# 04_SCAN.net
KiCad netlist of a schematic drawn in Altium Designer
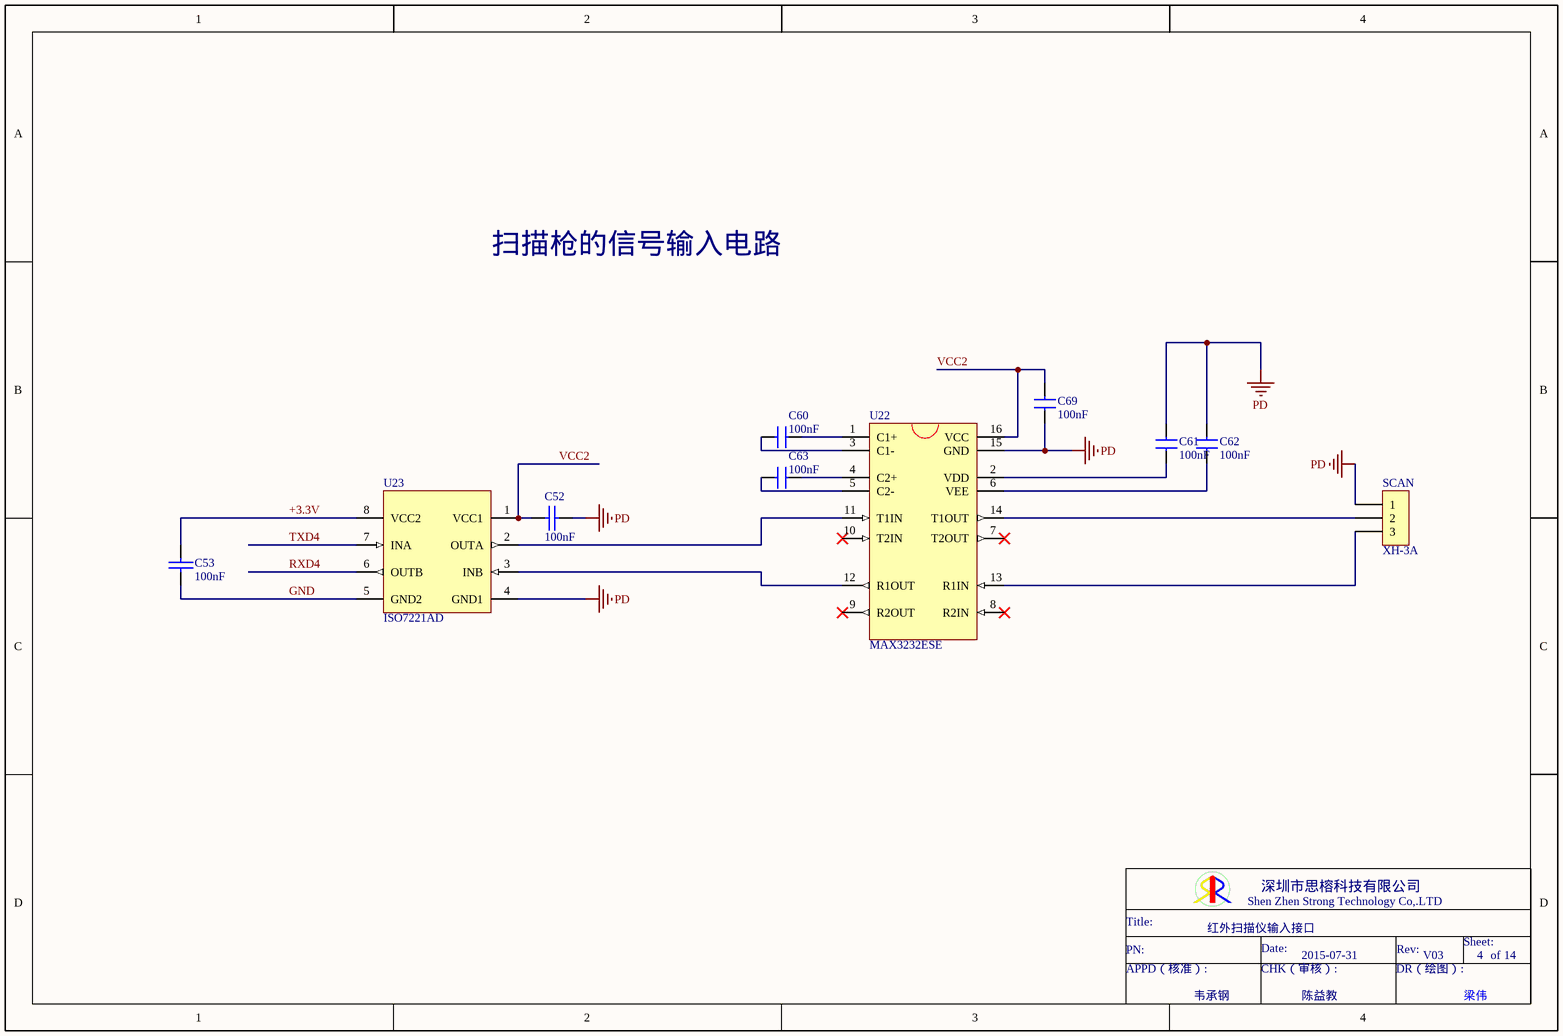
[diagram p0: 04_SCAN.SchDoc]

(export (version "E")
  (design (tool "Eeschema 10.0.6"))
  (components
    (comp (ref "C52") (value "100nF") (footprint "0603C") (libsource (lib "WeiCHGSCH") (part "CAP")))
    (comp (ref "C53") (value "100nF") (footprint "0603C") (libsource (lib "WeiCHGSCH") (part "CAP")))
    (comp (ref "C60")
      (value "100nF")
      (footprint "0603C")
      (description "Capacitor")
      (libsource (lib "*") (part "电容"))
    )
    (comp (ref "C61")
      (value "100nF")
      (footprint "0603C")
      (description "Capacitor")
      (libsource (lib "*") (part "电容"))
    )
    (comp (ref "C62")
      (value "100nF")
      (footprint "0603C")
      (description "Capacitor")
      (libsource (lib "*") (part "电容"))
    )
    (comp (ref "C63")
      (value "100nF")
      (footprint "0603C")
      (description "Capacitor")
      (libsource (lib "*") (part "电容"))
    )
    (comp (ref "C69")
      (value "100nF")
      (footprint "0603C")
      (description "Capacitor")
      (libsource (lib "*") (part "电容"))
    )
    (comp (ref "SCAN") (value "XH-3A") (footprint "CN3-2.54") (libsource (lib "Mylibrary") (part "CON3")))
    (comp (ref "U22")
      (value "MAX3232ESE")
      (footprint "SOP16")
      (description "SP3232")
      (fields (field (name "PUBLISHER") "Altium Limited"))
      (libsource (lib "LGA") (part "U101"))
    )
    (comp (ref "U23")
      (value "ISO7221AD")
      (footprint "SOP8")
      (libsource (lib "ISO7221xD") (part "Component_1"))
    )
  )
  (nets
    (net (code "1") (name "/+3.3V") (class "Default")
      (node (ref "C53") (pin "2") (pinfunction "2_2") (pintype "passive"))
      (node (ref "U23") (pin "8") (pinfunction "VCC2_8") (pintype "passive"))
    )
    (net (code "2") (name "/GND") (class "Default")
      (node (ref "C53") (pin "1") (pinfunction "1_1") (pintype "passive"))
      (node (ref "U23") (pin "5") (pinfunction "GND2_5") (pintype "passive"))
    )
    (net (code "3") (name "/RXD4") (class "Default")
      (node (ref "U23") (pin "6") (pinfunction "OUTB_6") (pintype "output"))
    )
    (net (code "4") (name "/TXD4") (class "Default")
      (node (ref "U23") (pin "7") (pinfunction "INA_7") (pintype "input"))
    )
    (net (code "5") (name "/VCC2") (class "Default")
      (node (ref "C52") (pin "1") (pinfunction "1_1") (pintype "passive"))
      (node (ref "C69") (pin "1") (pinfunction "1_1") (pintype "passive"))
      (node (ref "U22") (pin "16") (pinfunction "VCC_16") (pintype "power_in"))
      (node (ref "U23") (pin "1") (pinfunction "VCC1_1") (pintype "passive"))
    )
    (net (code "6") (name "Net-(U22-C1+)") (class "Default")
      (node (ref "C60") (pin "2") (pinfunction "2_2") (pintype "passive"))
      (node (ref "U22") (pin "1") (pinfunction "C1+_1") (pintype "passive"))
    )
    (net (code "7") (name "Net-(U22-C1-)") (class "Default")
      (node (ref "C60") (pin "1") (pinfunction "1_1") (pintype "passive"))
      (node (ref "U22") (pin "3") (pinfunction "C1-_3") (pintype "passive"))
    )
    (net (code "8") (name "Net-(U22-C2+)") (class "Default")
      (node (ref "C63") (pin "1") (pinfunction "1_1") (pintype "passive"))
      (node (ref "U22") (pin "4") (pinfunction "C2+_4") (pintype "passive"))
    )
    (net (code "9") (name "Net-(U22-C2-)") (class "Default")
      (node (ref "C63") (pin "2") (pinfunction "2_2") (pintype "passive"))
      (node (ref "U22") (pin "5") (pinfunction "C2-_5") (pintype "passive"))
    )
    (net (code "10") (name "Net-(U22-R1IN)") (class "Default")
      (node (ref "SCAN") (pin "3") (pinfunction "3_3") (pintype "passive"))
      (node (ref "U22") (pin "13") (pinfunction "R1IN_13") (pintype "input"))
    )
    (net (code "11") (name "Net-(U22-R1OUT)") (class "Default")
      (node (ref "U22") (pin "12") (pinfunction "R1OUT_12") (pintype "output"))
      (node (ref "U23") (pin "3") (pinfunction "INB_3") (pintype "input"))
    )
    (net (code "12") (name "Net-(U22-T1IN)") (class "Default")
      (node (ref "U22") (pin "11") (pinfunction "T1IN_11") (pintype "input"))
      (node (ref "U23") (pin "2") (pinfunction "OUTA_2") (pintype "output"))
    )
    (net (code "13") (name "Net-(U22-T1OUT)") (class "Default")
      (node (ref "SCAN") (pin "2") (pinfunction "2_2") (pintype "passive"))
      (node (ref "U22") (pin "14") (pinfunction "T1OUT_14") (pintype "output"))
    )
    (net (code "14") (name "Net-(U22-VDD)") (class "Default")
      (node (ref "C61") (pin "1") (pinfunction "1_1") (pintype "passive"))
      (node (ref "U22") (pin "2") (pinfunction "VDD_2") (pintype "power_in"))
    )
    (net (code "15") (name "Net-(U22-VEE)") (class "Default")
      (node (ref "C62") (pin "1") (pinfunction "1_1") (pintype "passive"))
      (node (ref "U22") (pin "6") (pinfunction "VEE_6") (pintype "power_in"))
    )
    (net (code "16") (name "PD") (class "Default")
      (node (ref "C52") (pin "2") (pinfunction "2_2") (pintype "passive"))
      (node (ref "C61") (pin "2") (pinfunction "2_2") (pintype "passive"))
      (node (ref "C62") (pin "2") (pinfunction "2_2") (pintype "passive"))
      (node (ref "C69") (pin "2") (pinfunction "2_2") (pintype "passive"))
      (node (ref "SCAN") (pin "1") (pinfunction "1_1") (pintype "passive"))
      (node (ref "U22") (pin "15") (pinfunction "GND_15") (pintype "power_in"))
      (node (ref "U23") (pin "4") (pinfunction "GND1_4") (pintype "passive"))
    )
    (net (code "17") (name "unconnected-(U22-R2IN-Pad8)") (class "Default")
      (node (ref "U22") (pin "8") (pinfunction "R2IN_8") (pintype "input+no_connect"))
    )
    (net (code "18") (name "unconnected-(U22-R2OUT-Pad9)") (class "Default")
      (node (ref "U22") (pin "9") (pinfunction "R2OUT_9") (pintype "output+no_connect"))
    )
    (net (code "19") (name "unconnected-(U22-T2IN-Pad10)") (class "Default")
      (node (ref "U22") (pin "10") (pinfunction "T2IN_10") (pintype "input+no_connect"))
    )
    (net (code "20") (name "unconnected-(U22-T2OUT-Pad7)") (class "Default")
      (node (ref "U22") (pin "7") (pinfunction "T2OUT_7") (pintype "output+no_connect"))
    )
  )
)
